# ZS6TVB_Arduino_AX_25_Interface_REV_1_0.net
KiCad netlist of a schematic drawn in EAGLE
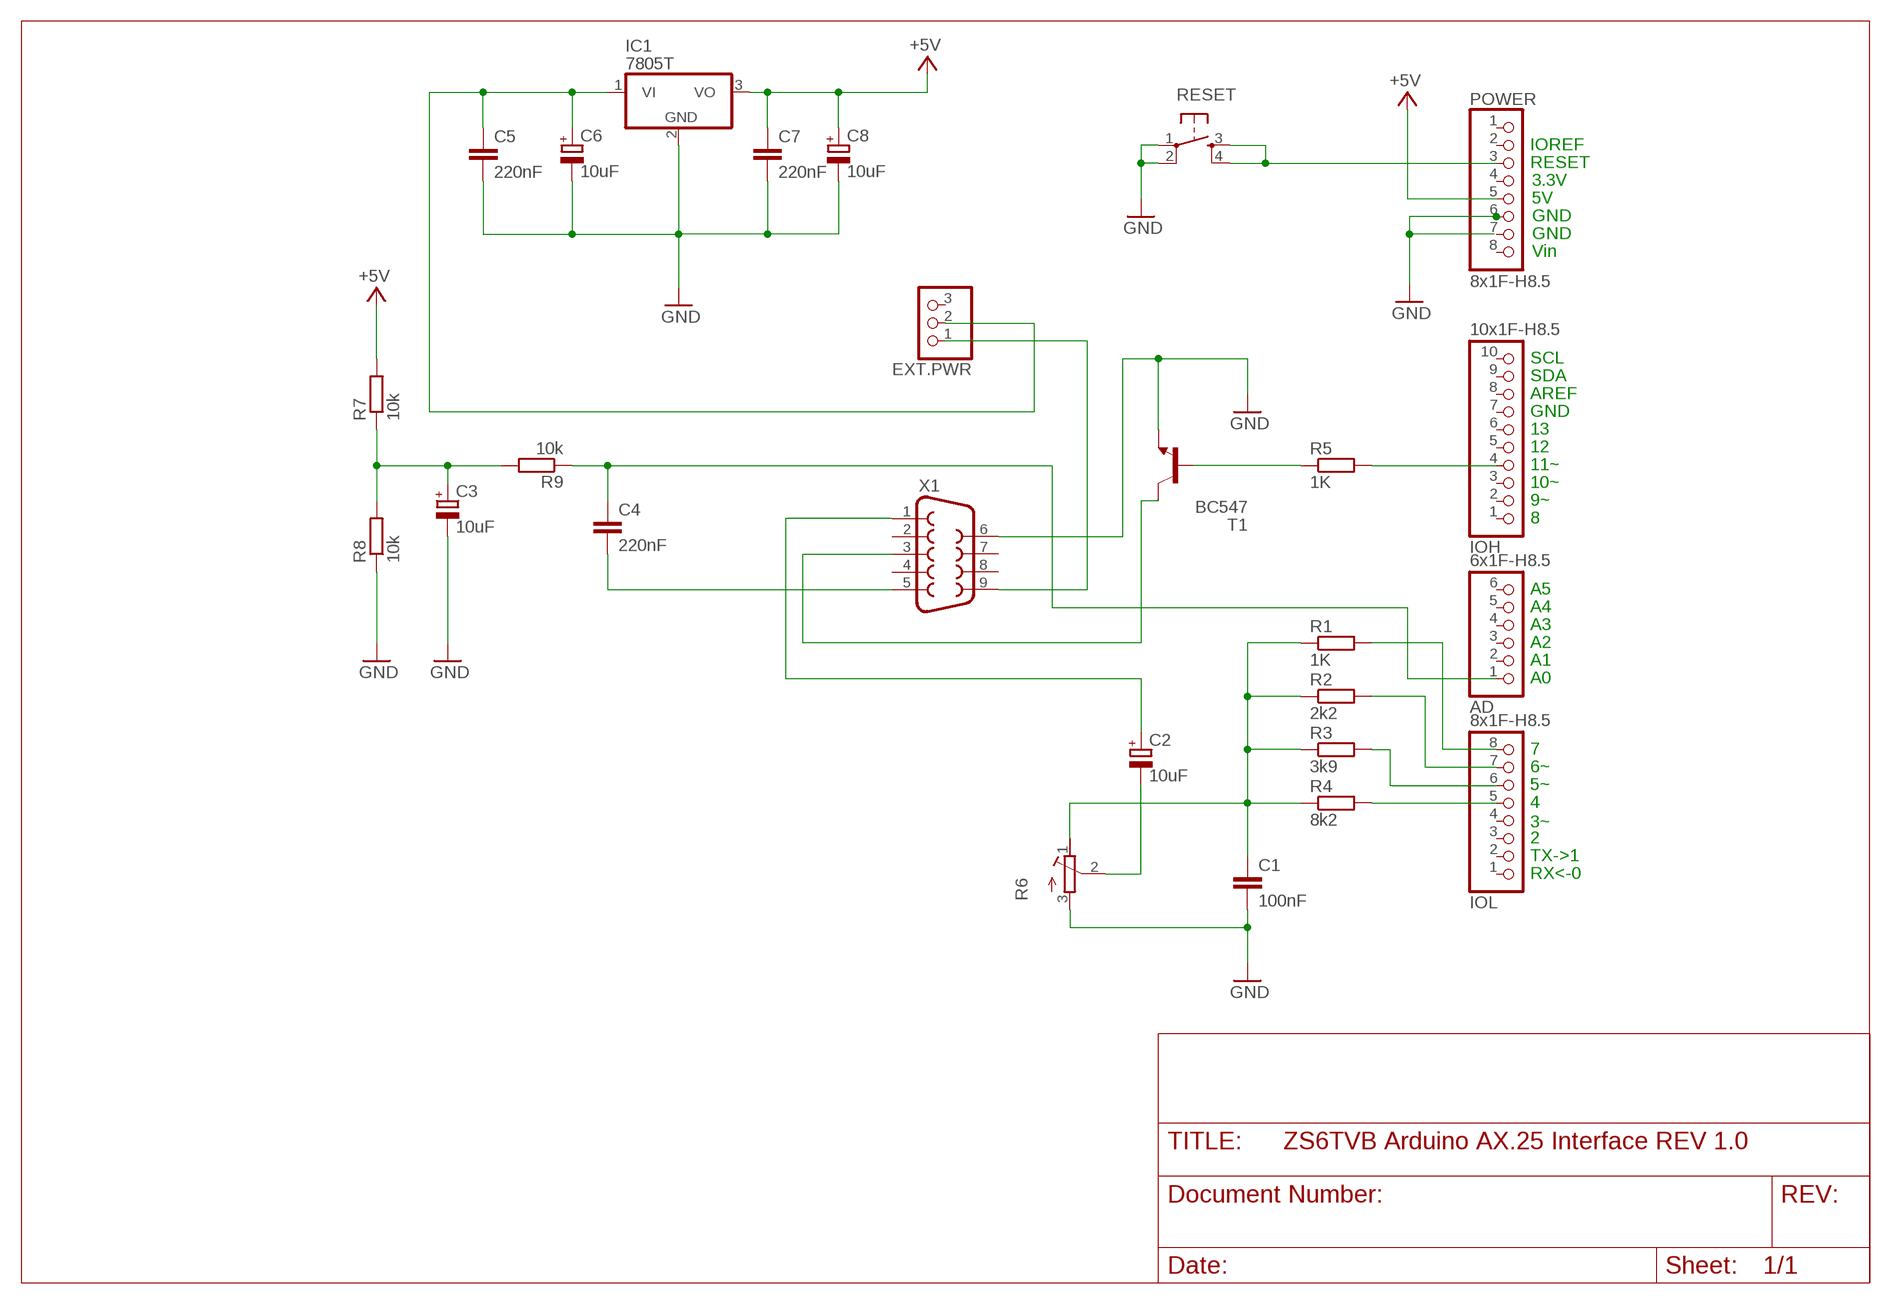
[diagram p0: schematic, sheet 1]

(export (version "E")
  (design (tool "Eeschema 10.0.6"))
  (components
    (comp (ref "AD")
      (value "6x1F-H8.5")
      (footprint "eagle-import:1X06")
      (libsource (lib "eagle-import") (part "PINHD-1X6"))
    )
    (comp (ref "C1")
      (value "100nF")
      (footprint "eagle-import:C050-024X044")
      (libsource (lib "eagle-import") (part "C-EU050-024X044"))
    )
    (comp (ref "C2")
      (value "10uF")
      (footprint "eagle-import:E5-10,5")
      (libsource (lib "eagle-import") (part "CPOL-EUE5-10.5"))
    )
    (comp (ref "C3")
      (value "10uF")
      (footprint "eagle-import:E5-10,5")
      (libsource (lib "eagle-import") (part "CPOL-EUE5-10.5"))
    )
    (comp (ref "C4")
      (value "220nF")
      (footprint "eagle-import:C050-024X044")
      (libsource (lib "eagle-import") (part "C-EU050-024X044"))
    )
    (comp (ref "C5")
      (value "220nF")
      (footprint "eagle-import:C050-024X044")
      (libsource (lib "eagle-import") (part "C-EU050-024X044"))
    )
    (comp (ref "C6")
      (value "10uF")
      (footprint "eagle-import:E5-10,5")
      (libsource (lib "eagle-import") (part "CPOL-EUE5-10.5"))
    )
    (comp (ref "C7")
      (value "220nF")
      (footprint "eagle-import:C050-024X044")
      (libsource (lib "eagle-import") (part "C-EU050-024X044"))
    )
    (comp (ref "C8")
      (value "10uF")
      (footprint "eagle-import:E5-10,5")
      (libsource (lib "eagle-import") (part "CPOL-EUE5-10.5"))
    )
    (comp (ref "EXT.PWR")
      (value "PINHD-1X3")
      (footprint "eagle-import:1X03")
      (libsource (lib "eagle-import") (part "PINHD-1X3"))
    )
    (comp (ref "IC1")
      (value "7805T")
      (footprint "eagle-import:TO220H")
      (libsource (lib "eagle-import") (part "78T05"))
    )
    (comp (ref "IOH")
      (value "10x1F-H8.5")
      (footprint "eagle-import:1X10")
      (libsource (lib "eagle-import") (part "PINHD-1X10_ARD"))
    )
    (comp (ref "IOL")
      (value "8x1F-H8.5")
      (footprint "eagle-import:1X08")
      (libsource (lib "eagle-import") (part "PINHD-1X8"))
    )
    (comp (ref "POWER")
      (value "8x1F-H8.5")
      (footprint "eagle-import:1X08")
      (libsource (lib "eagle-import") (part "PINHD-1X8"))
    )
    (comp (ref "R1")
      (value "1K")
      (footprint "eagle-import:0207_7")
      (libsource (lib "eagle-import") (part "R-EU_0207/7"))
    )
    (comp (ref "R2")
      (value "2k2")
      (footprint "eagle-import:0207_7")
      (libsource (lib "eagle-import") (part "R-EU_0207/7"))
    )
    (comp (ref "R3")
      (value "3k9")
      (footprint "eagle-import:0207_7")
      (libsource (lib "eagle-import") (part "R-EU_0207/7"))
    )
    (comp (ref "R4")
      (value "8k2")
      (footprint "eagle-import:0207_7")
      (libsource (lib "eagle-import") (part "R-EU_0207/7"))
    )
    (comp (ref "R5")
      (value "1K")
      (footprint "eagle-import:0207_7")
      (libsource (lib "eagle-import") (part "R-EU_0207/7"))
    )
    (comp (ref "R6")
      (value "R-TRIMMT93XB")
      (footprint "eagle-import:RTRIMT93XB")
      (libsource (lib "eagle-import") (part "R-TRIMMT93XB"))
    )
    (comp (ref "R7")
      (value "10k")
      (footprint "eagle-import:0207_7")
      (libsource (lib "eagle-import") (part "R-EU_0207/7"))
    )
    (comp (ref "R8")
      (value "10k")
      (footprint "eagle-import:0207_7")
      (libsource (lib "eagle-import") (part "R-EU_0207/7"))
    )
    (comp (ref "R9")
      (value "10k")
      (footprint "eagle-import:0207_7")
      (libsource (lib "eagle-import") (part "R-EU_0207/7"))
    )
    (comp (ref "RESET")
      (value "TAC_SWITCHPTH")
      (footprint "eagle-import:TACTILE-PTH")
      (libsource (lib "eagle-import") (part "TAC_SWITCHPTH"))
    )
    (comp (ref "T1")
      (value "BC547")
      (footprint "eagle-import:TO92")
      (libsource (lib "eagle-import") (part "BC547"))
    )
    (comp (ref "X1")
      (value "F09HP")
      (footprint "eagle-import:F09HP")
      (libsource (lib "eagle-import") (part "F09HP"))
    )
  )
  (nets
    (net (code "1") (name "+5V") (class "Default")
      (node (ref "C7") (pin "1") (pinfunction "1_1") (pintype "passive"))
      (node (ref "C8") (pin "+") (pinfunction "+_+") (pintype "passive"))
      (node (ref "IC1") (pin "3") (pinfunction "VO_3") (pintype "passive"))
      (node (ref "POWER") (pin "5") (pinfunction "5_5") (pintype "passive"))
      (node (ref "R7") (pin "2") (pinfunction "2_2") (pintype "passive"))
    )
    (net (code "2") (name "GND") (class "Default")
      (node (ref "C1") (pin "2") (pinfunction "2_2") (pintype "passive"))
      (node (ref "C3") (pin "-") (pinfunction "-_-") (pintype "passive"))
      (node (ref "C5") (pin "2") (pinfunction "2_2") (pintype "passive"))
      (node (ref "C6") (pin "-") (pinfunction "-_-") (pintype "passive"))
      (node (ref "C7") (pin "2") (pinfunction "2_2") (pintype "passive"))
      (node (ref "C8") (pin "-") (pinfunction "-_-") (pintype "passive"))
      (node (ref "IC1") (pin "2") (pinfunction "GND_2") (pintype "passive"))
      (node (ref "POWER") (pin "6") (pinfunction "6_6") (pintype "passive"))
      (node (ref "R6") (pin "3") (pinfunction "A_3") (pintype "passive"))
      (node (ref "R8") (pin "1") (pinfunction "1_1") (pintype "passive"))
      (node (ref "RESET") (pin "1") (pinfunction "1_1") (pintype "passive"))
      (node (ref "RESET") (pin "2") (pinfunction "2_2") (pintype "passive"))
      (node (ref "T1") (pin "1") (pinfunction "E_1") (pintype "passive"))
      (node (ref "X1") (pin "6") (pinfunction "6_6") (pintype "passive"))
    )
    (net (code "3") (name "Net-(AD-Pad1)") (class "Default")
      (node (ref "AD") (pin "1") (pinfunction "1_1") (pintype "passive"))
      (node (ref "C4") (pin "1") (pinfunction "1_1") (pintype "passive"))
      (node (ref "R9") (pin "1") (pinfunction "1_1") (pintype "passive"))
    )
    (net (code "4") (name "Net-(C2-Pad+)") (class "Default")
      (node (ref "C2") (pin "+") (pinfunction "+_+") (pintype "passive"))
      (node (ref "X1") (pin "1") (pinfunction "1_1") (pintype "passive"))
    )
    (net (code "5") (name "Net-(C3-Pad+)") (class "Default")
      (node (ref "C3") (pin "+") (pinfunction "+_+") (pintype "passive"))
      (node (ref "R7") (pin "1") (pinfunction "1_1") (pintype "passive"))
      (node (ref "R8") (pin "2") (pinfunction "2_2") (pintype "passive"))
      (node (ref "R9") (pin "2") (pinfunction "2_2") (pintype "passive"))
    )
    (net (code "6") (name "Net-(C4-Pad2)") (class "Default")
      (node (ref "C4") (pin "2") (pinfunction "2_2") (pintype "passive"))
      (node (ref "X1") (pin "5") (pinfunction "5_5") (pintype "passive"))
    )
    (net (code "7") (name "Net-(EXT.PWR-Pad1)") (class "Default")
      (node (ref "EXT.PWR") (pin "1") (pinfunction "1_1") (pintype "passive"))
      (node (ref "X1") (pin "9") (pinfunction "9_9") (pintype "passive"))
    )
    (net (code "8") (name "Net-(IC1-VI)") (class "Default")
      (node (ref "C5") (pin "1") (pinfunction "1_1") (pintype "passive"))
      (node (ref "C6") (pin "+") (pinfunction "+_+") (pintype "passive"))
      (node (ref "EXT.PWR") (pin "2") (pinfunction "2_2") (pintype "passive"))
      (node (ref "IC1") (pin "1") (pinfunction "VI_1") (pintype "input"))
    )
    (net (code "9") (name "Net-(IOH-Pad4)") (class "Default")
      (node (ref "IOH") (pin "4") (pinfunction "4_4") (pintype "passive"))
      (node (ref "R5") (pin "2") (pinfunction "2_2") (pintype "passive"))
    )
    (net (code "10") (name "Net-(IOL-Pad5)") (class "Default")
      (node (ref "IOL") (pin "5") (pinfunction "5_5") (pintype "passive"))
      (node (ref "R4") (pin "2") (pinfunction "2_2") (pintype "passive"))
    )
    (net (code "11") (name "Net-(IOL-Pad6)") (class "Default")
      (node (ref "IOL") (pin "6") (pinfunction "6_6") (pintype "passive"))
      (node (ref "R3") (pin "2") (pinfunction "2_2") (pintype "passive"))
    )
    (net (code "12") (name "Net-(IOL-Pad7)") (class "Default")
      (node (ref "IOL") (pin "7") (pinfunction "7_7") (pintype "passive"))
      (node (ref "R2") (pin "2") (pinfunction "2_2") (pintype "passive"))
    )
    (net (code "13") (name "Net-(IOL-Pad8)") (class "Default")
      (node (ref "IOL") (pin "8") (pinfunction "8_8") (pintype "passive"))
      (node (ref "R1") (pin "2") (pinfunction "2_2") (pintype "passive"))
    )
    (net (code "14") (name "Net-(POWER-Pad3)") (class "Default")
      (node (ref "POWER") (pin "3") (pinfunction "3_3") (pintype "passive"))
      (node (ref "RESET") (pin "3") (pinfunction "3_3") (pintype "passive"))
      (node (ref "RESET") (pin "4") (pinfunction "4_4") (pintype "passive"))
    )
    (net (code "15") (name "Net-(R6-E)") (class "Default")
      (node (ref "C1") (pin "1") (pinfunction "1_1") (pintype "passive"))
      (node (ref "R1") (pin "1") (pinfunction "1_1") (pintype "passive"))
      (node (ref "R2") (pin "1") (pinfunction "1_1") (pintype "passive"))
      (node (ref "R3") (pin "1") (pinfunction "1_1") (pintype "passive"))
      (node (ref "R4") (pin "1") (pinfunction "1_1") (pintype "passive"))
      (node (ref "R6") (pin "1") (pinfunction "E_1") (pintype "passive"))
    )
    (net (code "16") (name "Net-(R6-S)") (class "Default")
      (node (ref "C2") (pin "-") (pinfunction "-_-") (pintype "passive"))
      (node (ref "R6") (pin "2") (pinfunction "S_2") (pintype "passive"))
    )
    (net (code "17") (name "Net-(T1-B)") (class "Default")
      (node (ref "R5") (pin "1") (pinfunction "1_1") (pintype "passive"))
      (node (ref "T1") (pin "2") (pinfunction "B_2") (pintype "passive"))
    )
    (net (code "18") (name "Net-(T1-C)") (class "Default")
      (node (ref "T1") (pin "3") (pinfunction "C_3") (pintype "passive"))
      (node (ref "X1") (pin "3") (pinfunction "3_3") (pintype "passive"))
    )
    (net (code "19") (name "unconnected-(AD-Pad2)") (class "Default")
      (node (ref "AD") (pin "2") (pinfunction "2_2") (pintype "passive"))
    )
    (net (code "20") (name "unconnected-(AD-Pad3)") (class "Default")
      (node (ref "AD") (pin "3") (pinfunction "3_3") (pintype "passive"))
    )
    (net (code "21") (name "unconnected-(AD-Pad4)") (class "Default")
      (node (ref "AD") (pin "4") (pinfunction "4_4") (pintype "passive"))
    )
    (net (code "22") (name "unconnected-(AD-Pad5)") (class "Default")
      (node (ref "AD") (pin "5") (pinfunction "5_5") (pintype "passive"))
    )
    (net (code "23") (name "unconnected-(AD-Pad6)") (class "Default")
      (node (ref "AD") (pin "6") (pinfunction "6_6") (pintype "passive"))
    )
    (net (code "24") (name "unconnected-(EXT.PWR-Pad3)") (class "Default")
      (node (ref "EXT.PWR") (pin "3") (pinfunction "3_3") (pintype "passive"))
    )
    (net (code "25") (name "unconnected-(IOH-Pad1)") (class "Default")
      (node (ref "IOH") (pin "1") (pinfunction "1_1") (pintype "passive"))
    )
    (net (code "26") (name "unconnected-(IOH-Pad2)") (class "Default")
      (node (ref "IOH") (pin "2") (pinfunction "2_2") (pintype "passive"))
    )
    (net (code "27") (name "unconnected-(IOH-Pad3)") (class "Default")
      (node (ref "IOH") (pin "3") (pinfunction "3_3") (pintype "passive"))
    )
    (net (code "28") (name "unconnected-(IOH-Pad5)") (class "Default")
      (node (ref "IOH") (pin "5") (pinfunction "5_5") (pintype "passive"))
    )
    (net (code "29") (name "unconnected-(IOH-Pad6)") (class "Default")
      (node (ref "IOH") (pin "6") (pinfunction "6_6") (pintype "passive"))
    )
    (net (code "30") (name "unconnected-(IOH-Pad7)") (class "Default")
      (node (ref "IOH") (pin "7") (pinfunction "7_7") (pintype "passive"))
    )
    (net (code "31") (name "unconnected-(IOH-Pad8)") (class "Default")
      (node (ref "IOH") (pin "8") (pinfunction "8_8") (pintype "passive"))
    )
    (net (code "32") (name "unconnected-(IOH-Pad9)") (class "Default")
      (node (ref "IOH") (pin "9") (pinfunction "9_9") (pintype "passive"))
    )
    (net (code "33") (name "unconnected-(IOH-Pad10)") (class "Default")
      (node (ref "IOH") (pin "10") (pinfunction "10_10") (pintype "passive"))
    )
    (net (code "34") (name "unconnected-(IOL-Pad1)") (class "Default")
      (node (ref "IOL") (pin "1") (pinfunction "1_1") (pintype "passive"))
    )
    (net (code "35") (name "unconnected-(IOL-Pad2)") (class "Default")
      (node (ref "IOL") (pin "2") (pinfunction "2_2") (pintype "passive"))
    )
    (net (code "36") (name "unconnected-(IOL-Pad3)") (class "Default")
      (node (ref "IOL") (pin "3") (pinfunction "3_3") (pintype "passive"))
    )
    (net (code "37") (name "unconnected-(IOL-Pad4)") (class "Default")
      (node (ref "IOL") (pin "4") (pinfunction "4_4") (pintype "passive"))
    )
    (net (code "38") (name "unconnected-(POWER-Pad1)") (class "Default")
      (node (ref "POWER") (pin "1") (pinfunction "1_1") (pintype "passive"))
    )
    (net (code "39") (name "unconnected-(POWER-Pad2)") (class "Default")
      (node (ref "POWER") (pin "2") (pinfunction "2_2") (pintype "passive"))
    )
    (net (code "40") (name "unconnected-(POWER-Pad4)") (class "Default")
      (node (ref "POWER") (pin "4") (pinfunction "4_4") (pintype "passive"))
    )
    (net (code "41") (name "unconnected-(POWER-Pad7)") (class "Default")
      (node (ref "POWER") (pin "7") (pinfunction "7_7") (pintype "passive"))
    )
    (net (code "42") (name "unconnected-(POWER-Pad8)") (class "Default")
      (node (ref "POWER") (pin "8") (pinfunction "8_8") (pintype "passive"))
    )
    (net (code "43") (name "unconnected-(X1-Pad2)") (class "Default")
      (node (ref "X1") (pin "2") (pinfunction "2_2") (pintype "passive"))
    )
    (net (code "44") (name "unconnected-(X1-Pad4)") (class "Default")
      (node (ref "X1") (pin "4") (pinfunction "4_4") (pintype "passive"))
    )
    (net (code "45") (name "unconnected-(X1-Pad7)") (class "Default")
      (node (ref "X1") (pin "7") (pinfunction "7_7") (pintype "passive"))
    )
    (net (code "46") (name "unconnected-(X1-Pad8)") (class "Default")
      (node (ref "X1") (pin "8") (pinfunction "8_8") (pintype "passive"))
    )
  )
)
